# FT601.net
KiCad netlist of a schematic drawn in Altium Designer
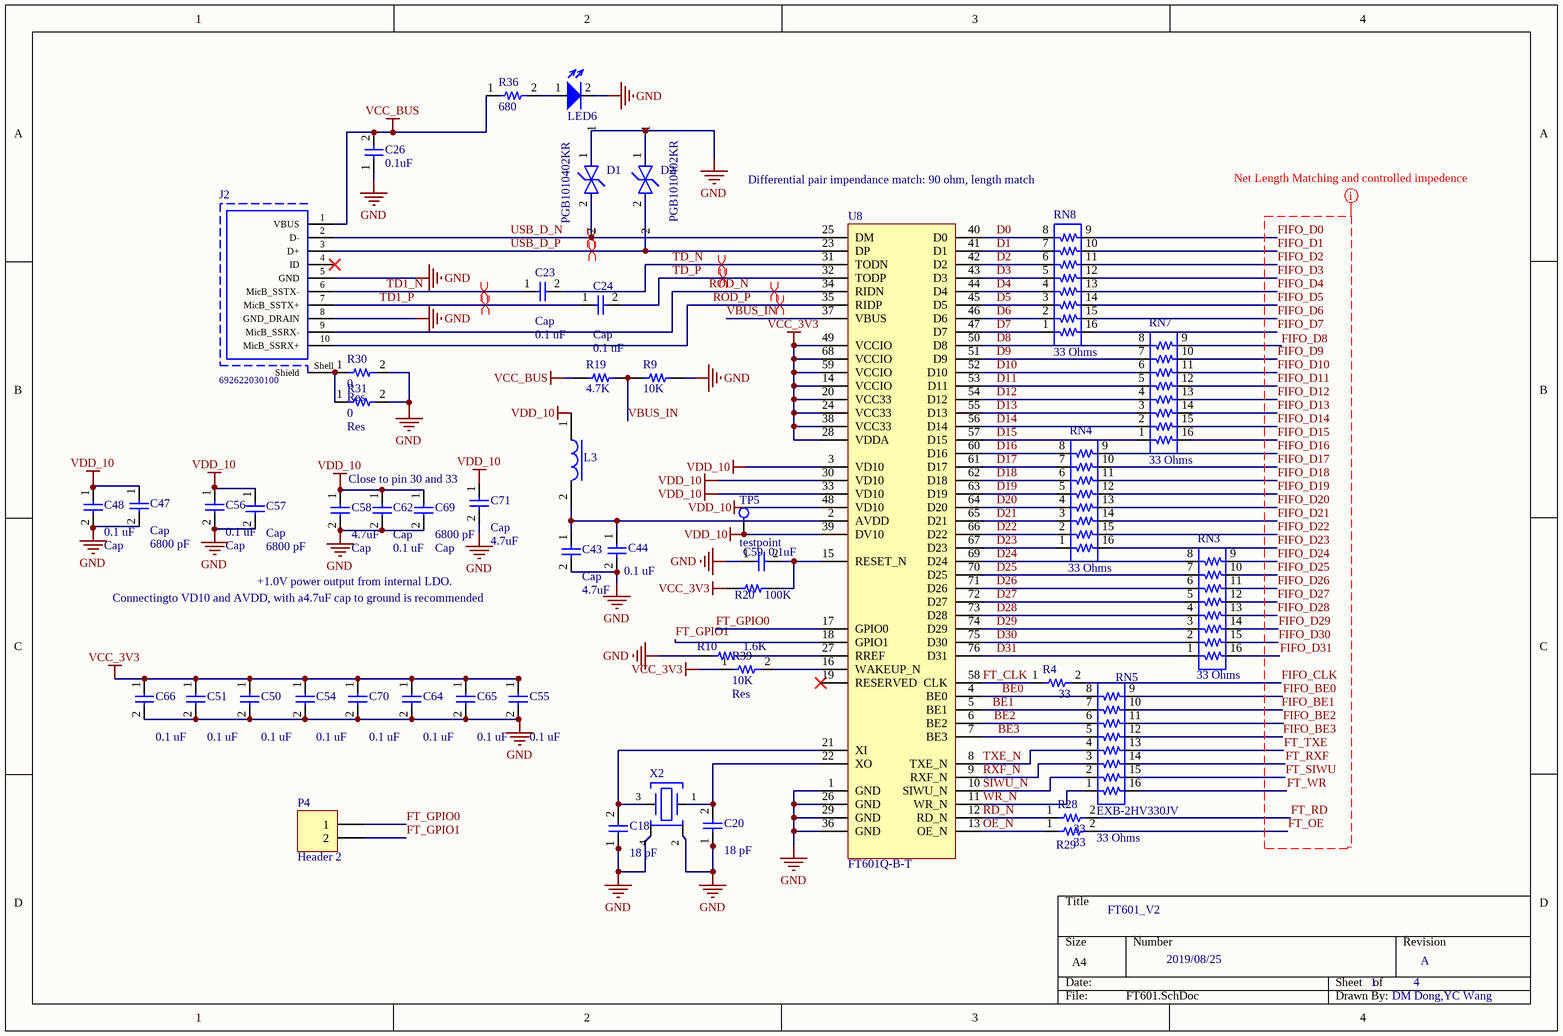
[diagram p0: FT601.SchDoc]

(export (version "E")
  (design (tool "Eeschema 10.0.6"))
  (components
    (comp (ref "C18")
      (value "18 pF")
      (footprint "CAP_18pF_0603")
      (description "Multilayer Ceramic Capacitors MLCC - SMD/SMT 50V 18pF 0603 X7R 10% AEC-Q200")
      (fields (field (name "Comment") "C0603C180K5RACAUTO"))
      (libsource (lib "USB_FPGA_SLM_v1") (part "Cap_18pF_0603"))
    )
    (comp (ref "C20")
      (value "18 pF")
      (footprint "CAP_18pF_0603")
      (description "Multilayer Ceramic Capacitors MLCC - SMD/SMT 50V 18pF 0603 X7R 10% AEC-Q200")
      (fields (field (name "Comment") "C0603C180K5RACAUTO"))
      (libsource (lib "USB_FPGA_SLM_v1") (part "Cap_18pF_0603"))
    )
    (comp (ref "C23")
      (value "0.1 uF")
      (footprint "Cap_0.1uF_0402")
      (description "Multilayer Ceramic Capacitors MLCC - SMD/SMT 100nF 10V X5R 10%")
      (fields
        (field (name "COMPONENT NAME") "Cap")
        (field (name "Comment") "CC0402KPX5R6BB104")
        (field (name "CREATED BY") "Daoming Dong")
      )
      (libsource (lib "USB_FPGA_SLM_v1") (part "CAP_0.1uF_0402"))
    )
    (comp (ref "C24")
      (value "0.1 uF")
      (footprint "Cap_0.1uF_0402")
      (description "Multilayer Ceramic Capacitors MLCC - SMD/SMT 100nF 10V X5R 10%")
      (fields
        (field (name "COMPONENT NAME") "Cap")
        (field (name "Comment") "CC0402KPX5R6BB104")
        (field (name "CREATED BY") "Daoming Dong")
      )
      (libsource (lib "USB_FPGA_SLM_v1") (part "CAP_0.1uF_0402"))
    )
    (comp (ref "C26")
      (value "0.1uF")
      (footprint "Cap_0.1uF")
      (description "Multilayer Ceramic Capacitors MLCC - SMD/SMT 0.1uF 10% 50V AEC-Q200")
      (fields (field (name "Comment") "AC0603KRX7R9BB104") (field (name "CREATED BY") "Daoming Dong"))
      (libsource (lib "USB_FPGA_SLM_v1") (part "Cap_0.1uF"))
    )
    (comp (ref "C43")
      (value "4.7uF")
      (footprint "CAP_4.7uF_0402")
      (description "Multilayer Ceramic Capacitors MLCC - SMD/SMT 0402 6.3V 4.7uF X5R 10% T: 0.5mm")
      (fields
        (field (name "COMPONENT NAME") "Cap")
        (field (name "Comment") "C1005X5R0J475K050BC")
        (field (name "CREATED BY") "Daoming Dong")
      )
      (libsource (lib "USB_FPGA_SLM_v1") (part "Cap_4.7uF_0402"))
    )
    (comp (ref "C44")
      (value "0.1 uF")
      (footprint "Cap_0.1uF_0402")
      (description "Multilayer Ceramic Capacitors MLCC - SMD/SMT 100nF 10V X5R 10%")
      (fields (field (name "Comment") "CC0402KPX5R6BB104") (field (name "CREATED BY") "Daoming Dong"))
      (libsource (lib "USB_FPGA_SLM_v1") (part "CAP_0.1uF_0402"))
    )
    (comp (ref "C47")
      (value "6800 pF")
      (footprint "CAP_6700pF_0402")
      (description "Multilayer Ceramic Capacitors MLCC - SMD/SMT 50V 6800pF X7R 0402 10% AEC-Q200")
      (fields
        (field (name "COMPONENT NAME") "Cap")
        (field (name "Comment") "C0402C682K5RECAUTO")
        (field (name "CREATED BY") "Daoming Dong")
      )
      (libsource (lib "USB_FPGA_SLM_v1") (part "Cap_6800pF_0402"))
    )
    (comp (ref "C48")
      (value "0.1 uF")
      (footprint "Cap_0.1uF_0402")
      (description "Multilayer Ceramic Capacitors MLCC - SMD/SMT 100nF 10V X5R 10%")
      (fields
        (field (name "COMPONENT NAME") "Cap")
        (field (name "Comment") "CC0402KPX5R6BB104")
        (field (name "CREATED BY") "Daoming Dong")
      )
      (libsource (lib "USB_FPGA_SLM_v1") (part "CAP_0.1uF_0402"))
    )
    (comp (ref "C50")
      (value "0.1 uF")
      (footprint "Cap_0.1uF_0402")
      (description "Multilayer Ceramic Capacitors MLCC - SMD/SMT 100nF 10V X5R 10%")
      (fields (field (name "Comment") "CC0402KPX5R6BB104") (field (name "CREATED BY") "Daoming Dong"))
      (libsource (lib "USB_FPGA_SLM_v1") (part "CAP_0.1uF_0402"))
    )
    (comp (ref "C51")
      (value "0.1 uF")
      (footprint "Cap_0.1uF_0402")
      (description "Multilayer Ceramic Capacitors MLCC - SMD/SMT 100nF 10V X5R 10%")
      (fields (field (name "Comment") "CC0402KPX5R6BB104") (field (name "CREATED BY") "Daoming Dong"))
      (libsource (lib "USB_FPGA_SLM_v1") (part "CAP_0.1uF_0402"))
    )
    (comp (ref "C54")
      (value "0.1 uF")
      (footprint "Cap_0.1uF_0402")
      (description "Multilayer Ceramic Capacitors MLCC - SMD/SMT 100nF 10V X5R 10%")
      (fields (field (name "Comment") "CC0402KPX5R6BB104") (field (name "CREATED BY") "Daoming Dong"))
      (libsource (lib "USB_FPGA_SLM_v1") (part "CAP_0.1uF_0402"))
    )
    (comp (ref "C55")
      (value "0.1 uF")
      (footprint "Cap_0.1uF_0402")
      (description "Multilayer Ceramic Capacitors MLCC - SMD/SMT 100nF 10V X5R 10%")
      (fields (field (name "Comment") "CC0402KPX5R6BB104") (field (name "CREATED BY") "Daoming Dong"))
      (libsource (lib "USB_FPGA_SLM_v1") (part "CAP_0.1uF_0402"))
    )
    (comp (ref "C56")
      (value "0.1 uF")
      (footprint "Cap_0.1uF_0402")
      (description "Multilayer Ceramic Capacitors MLCC - SMD/SMT 100nF 10V X5R 10%")
      (fields
        (field (name "COMPONENT NAME") "Cap")
        (field (name "Comment") "CC0402KPX5R6BB104")
        (field (name "CREATED BY") "Daoming Dong")
      )
      (libsource (lib "USB_FPGA_SLM_v1") (part "CAP_0.1uF_0402"))
    )
    (comp (ref "C57")
      (value "6800 pF")
      (footprint "CAP_6700pF_0402")
      (description "Multilayer Ceramic Capacitors MLCC - SMD/SMT 50V 6800pF X7R 0402 10% AEC-Q200")
      (fields
        (field (name "COMPONENT NAME") "Cap")
        (field (name "Comment") "C0402C682K5RECAUTO")
        (field (name "CREATED BY") "Daoming Dong")
      )
      (libsource (lib "USB_FPGA_SLM_v1") (part "Cap_6800pF_0402"))
    )
    (comp (ref "C58")
      (value "4.7uF")
      (footprint "CAP_4.7uF_0402")
      (description "Multilayer Ceramic Capacitors MLCC - SMD/SMT 0402 6.3V 4.7uF X5R 10% T: 0.5mm")
      (fields
        (field (name "COMPONENT NAME") "Cap")
        (field (name "Comment") "C1005X5R0J475K050BC")
        (field (name "CREATED BY") "Daoming Dong")
      )
      (libsource (lib "USB_FPGA_SLM_v1") (part "Cap_4.7uF_0402"))
    )
    (comp (ref "C59")
      (value "0.1uF")
      (footprint "Cap_0.1uF")
      (description "Multilayer Ceramic Capacitors MLCC - SMD/SMT 0.1uF 10% 50V AEC-Q200")
      (fields (field (name "Comment") "AC0603KRX7R9BB104") (field (name "CREATED BY") "Daoming Dong"))
      (libsource (lib "USB_FPGA_SLM_v1") (part "Cap_0.1uF"))
    )
    (comp (ref "C62")
      (value "0.1 uF")
      (footprint "Cap_0.1uF_0402")
      (description "Multilayer Ceramic Capacitors MLCC - SMD/SMT 100nF 10V X5R 10%")
      (fields
        (field (name "COMPONENT NAME") "Cap")
        (field (name "Comment") "CC0402KPX5R6BB104")
        (field (name "CREATED BY") "Daoming Dong")
      )
      (libsource (lib "USB_FPGA_SLM_v1") (part "CAP_0.1uF_0402"))
    )
    (comp (ref "C64")
      (value "0.1 uF")
      (footprint "Cap_0.1uF_0402")
      (description "Multilayer Ceramic Capacitors MLCC - SMD/SMT 100nF 10V X5R 10%")
      (fields (field (name "Comment") "CC0402KPX5R6BB104") (field (name "CREATED BY") "Daoming Dong"))
      (libsource (lib "USB_FPGA_SLM_v1") (part "CAP_0.1uF_0402"))
    )
    (comp (ref "C65")
      (value "0.1 uF")
      (footprint "Cap_0.1uF_0402")
      (description "Multilayer Ceramic Capacitors MLCC - SMD/SMT 100nF 10V X5R 10%")
      (fields (field (name "Comment") "CC0402KPX5R6BB104") (field (name "CREATED BY") "Daoming Dong"))
      (libsource (lib "USB_FPGA_SLM_v1") (part "CAP_0.1uF_0402"))
    )
    (comp (ref "C66")
      (value "0.1 uF")
      (footprint "Cap_0.1uF_0402")
      (description "Multilayer Ceramic Capacitors MLCC - SMD/SMT 100nF 10V X5R 10%")
      (fields (field (name "Comment") "CC0402KPX5R6BB104") (field (name "CREATED BY") "Daoming Dong"))
      (libsource (lib "USB_FPGA_SLM_v1") (part "CAP_0.1uF_0402"))
    )
    (comp (ref "C69")
      (value "6800 pF")
      (footprint "CAP_6700pF_0402")
      (description "Multilayer Ceramic Capacitors MLCC - SMD/SMT 50V 6800pF X7R 0402 10% AEC-Q200")
      (fields
        (field (name "COMPONENT NAME") "Cap")
        (field (name "Comment") "C0402C682K5RECAUTO")
        (field (name "CREATED BY") "Daoming Dong")
      )
      (libsource (lib "USB_FPGA_SLM_v1") (part "Cap_6800pF_0402"))
    )
    (comp (ref "C70")
      (value "0.1 uF")
      (footprint "Cap_0.1uF_0402")
      (description "Multilayer Ceramic Capacitors MLCC - SMD/SMT 100nF 10V X5R 10%")
      (fields (field (name "Comment") "CC0402KPX5R6BB104") (field (name "CREATED BY") "Daoming Dong"))
      (libsource (lib "USB_FPGA_SLM_v1") (part "CAP_0.1uF_0402"))
    )
    (comp (ref "C71")
      (value "4.7uF")
      (footprint "CAP_4.7uF_0402")
      (description "Multilayer Ceramic Capacitors MLCC - SMD/SMT 0402 6.3V 4.7uF X5R 10% T: 0.5mm")
      (fields
        (field (name "COMPONENT NAME") "Cap")
        (field (name "Comment") "C1005X5R0J475K050BC")
        (field (name "CREATED BY") "Daoming Dong")
      )
      (libsource (lib "USB_FPGA_SLM_v1") (part "Cap_4.7uF_0402"))
    )
    (comp (ref "D1")
      (value "PGB1010402KR")
      (footprint "ESD_Suppressor")
      (description "ESD Suppressors / TVS Diodes PULSEGUARD 0402 ESD SUPPRESSOR")
      (fields (field (name "CREATED BY") "Daoming Dong"))
      (libsource (lib "USB_FPGA_SLM_v1") (part "ESD_Suppresor"))
    )
    (comp (ref "D2")
      (value "PGB1010402KR")
      (footprint "ESD_Suppressor")
      (description "ESD Suppressors / TVS Diodes PULSEGUARD 0402 ESD SUPPRESSOR")
      (fields (field (name "CREATED BY") "Daoming Dong"))
      (libsource (lib "USB_FPGA_SLM_v1") (part "ESD_Suppresor"))
    )
    (comp (ref "J2")
      (value "692622030100")
      (footprint "692622030100")
      (description "Micro USB 3.0 Type B Receptacle WR-COM, Horizontal, SMT, with Pads")
      (fields (field (name "PUBLISHER") "Wurth Elektronik"))
      (libsource (lib "Altium_WR-COM_USB-Connectors (rev18d)") (part "692622030100"))
    )
    (comp (ref "L3")
      (value "BLM18PG300SZ1D")
      (footprint "FerriteBeads")
      (description "Ferrite Beads 0603 30ohms 1000mA Auto Infotainment")
      (fields (field (name "CREATED BY") "Daoming Dong"))
      (libsource (lib "USB_FPGA_SLM_v1") (part "FerriteBeadForFT601"))
    )
    (comp (ref "LED6")
      (value "TLMS1000-GS08")
      (footprint "LED_RED")
      (description "Standard LEDs - SMD RED")
      (fields (field (name "CREATED BY") "Daoming Dong"))
      (libsource (lib "USB_FPGA_SLM_v1") (part "LED_RED"))
    )
    (comp (ref "P4")
      (value "Header 2")
      (footprint "HDR1X2")
      (description "Header, 2-Pin")
      (fields (field (name "PUBLISHER") "Altium Limited"))
      (libsource (lib "Miscellaneous Connectors") (part "Header 2"))
    )
    (comp (ref "R4")
      (value "33")
      (footprint "Res_33_0402")
      (description "Thick Film Resistors - SMD 0402 Resistor 0.5% 100ppm 33Ohm")
      (fields (field (name "Comment") "ERJ2RKD33R0X") (field (name "CREATED BY.") "Daoming Dong"))
      (libsource (lib "USB_FPGA_SLM_v1") (part "Res_33_0402"))
    )
    (comp (ref "R9")
      (value "10K")
      (footprint "RES_10K")
      (description "Thin Film Resistors - SMD 10K ohm 0.05% 50 ppm High-Precision")
      (fields (field (name "Comment") "RT0603WRE0710KL") (field (name "CREATED BY") "Daoming Dong"))
      (libsource (lib "USB_FPGA_SLM_v1") (part "Res_10K"))
    )
    (comp (ref "R10")
      (value "1.6K")
      (footprint "RES_1.6K")
      (description "Thick Film Resistors - SMD 0603 Resistor 0.5% 50ppm 1.6KOhm")
      (fields (field (name "Comment") "ERJ-3RBD1601V") (field (name "CREATED BY") "Daoming Dong"))
      (libsource (lib "USB_FPGA_SLM_v1") (part "Res_1.6K"))
    )
    (comp (ref "R19")
      (value "4.7K")
      (footprint "RES_4.7K")
      (description "Thick Film Resistors - SMD 4.7K ohm 5% 1/10W AEC-Q200")
      (fields (field (name "Comment") "AC0603JR-134K7L") (field (name "CREATED BY") "Daoming Dong"))
      (libsource (lib "USB_FPGA_SLM_v1") (part "Res_4.7K"))
    )
    (comp (ref "R20")
      (value "100K")
      (footprint "RES_100K")
      (description "Thick Film Resistors - SMD 100K ohm 10% 75V AEC-Q200")
      (fields (field (name "Comment") "SR0603KR-07100KL") (field (name "CREATED BY") "Daoming Dong"))
      (libsource (lib "USB_FPGA_SLM_v1") (part "Res_100K"))
    )
    (comp (ref "R28")
      (value "33")
      (footprint "Res_33_0402")
      (description "Thick Film Resistors - SMD 0402 Resistor 0.5% 100ppm 33Ohm")
      (fields (field (name "Comment") "ERJ2RKD33R0X") (field (name "CREATED BY.") "Daoming Dong"))
      (libsource (lib "USB_FPGA_SLM_v1") (part "Res_33_0402"))
    )
    (comp (ref "R29")
      (value "33")
      (footprint "Res_33_0402")
      (description "Thick Film Resistors - SMD 0402 Resistor 0.5% 100ppm 33Ohm")
      (fields (field (name "Comment") "ERJ2RKD33R0X") (field (name "CREATED BY.") "Daoming Dong"))
      (libsource (lib "USB_FPGA_SLM_v1") (part "Res_33_0402"))
    )
    (comp (ref "R30")
      (value "0")
      (footprint "RES_0")
      (description "Thick Film Resistors - SMD 1/10Watt 0ohms Commercial Use")
      (fields
        (field (name "COMPONENT NAME") "Res")
        (field (name "Comment") "CRCW06030000Z0EAC")
        (field (name "CREATED BY") "Daoming Dong")
      )
      (libsource (lib "USB_FPGA_SLM_v1") (part "Res_0"))
    )
    (comp (ref "R31")
      (value "0")
      (footprint "RES_0")
      (description "Thick Film Resistors - SMD 1/10Watt 0ohms Commercial Use")
      (fields
        (field (name "COMPONENT NAME") "Res")
        (field (name "Comment") "CRCW06030000Z0EAC")
        (field (name "CREATED BY") "Daoming Dong")
      )
      (libsource (lib "USB_FPGA_SLM_v1") (part "Res_0"))
    )
    (comp (ref "R36")
      (value "680")
      (footprint "RES_680")
      (description "Thin Film Resistors - SMD 680 ohm 1% 50 ppm Thin Film")
      (fields (field (name "Comment") "RT0603FRE13680RL") (field (name "CREATED BY") "Daoming Dong"))
      (libsource (lib "USB_FPGA_SLM_v1") (part "Res_680"))
    )
    (comp (ref "R39")
      (value "10K")
      (footprint "RES_10K")
      (description "Thin Film Resistors - SMD 10K ohm 0.05% 50 ppm High-Precision")
      (fields
        (field (name "COMPONENT NAME") "Res")
        (field (name "Comment") "RT0603WRE0710KL")
        (field (name "CREATED BY") "Daoming Dong")
      )
      (libsource (lib "") (part "Res_10K_1"))
    )
    (comp (ref "RN3")
      (value "33 Ohms")
      (footprint "ResArray_0")
      (description "Resistor Networks & Arrays 33 OHM 5%")
      (fields (field (name "Comment") "EXB-2HV330JV"))
      (libsource (lib "USB_FPGA_SLM_v1") (part "ResArray"))
    )
    (comp (ref "RN4")
      (value "33 Ohms")
      (footprint "ResArray_0")
      (description "Resistor Networks & Arrays 33 OHM 5%")
      (fields (field (name "Comment") "EXB-2HV330JV"))
      (libsource (lib "USB_FPGA_SLM_v1") (part "ResArray"))
    )
    (comp (ref "RN5")
      (value "EXB-2HV330JV")
      (footprint "ResArray_0")
      (description "Resistor Networks & Arrays 33 OHM 5%")
      (fields (field (name "ALTIUM_VALUE") "33 Ohms"))
      (libsource (lib "USB_FPGA_SLM_v1") (part "ResArray"))
    )
    (comp (ref "RN7")
      (value "33 Ohms")
      (footprint "ResArray_0")
      (description "Resistor Networks & Arrays 33 OHM 5%")
      (fields (field (name "Comment") "EXB-2HV330JV"))
      (libsource (lib "USB_FPGA_SLM_v1") (part "ResArray"))
    )
    (comp (ref "RN8")
      (value "33 Ohms")
      (footprint "ResArray_0")
      (description "Resistor Networks & Arrays 33 OHM 5%")
      (fields (field (name "Comment") "EXB-2HV330JV"))
      (libsource (lib "USB_FPGA_SLM_v1") (part "ResArray"))
    )
    (comp (ref "TP5")
      (value "testpoint")
      (footprint "testpoint")
      (description "Testpoint for testing voltage")
      (fields (field (name "CREATED BY") "Daoming Dong"))
      (libsource (lib "USB_FPGA_SLM_v1") (part "Testpoint"))
    )
    (comp (ref "U8")
      (value "FT601Q-B-T")
      (footprint "FT601_NoGND_Pad")
      (description "USB Interface IC USB 3.0 Super-Speed 32Bits Sync FIFO")
      (fields (field (name "CREATED BY") "Daoming Dong"))
      (libsource (lib "USB_FPGA_SLM_v1") (part "FT601Q-B-T"))
    )
    (comp (ref "X2")
      (value "ABM8G-30.000MHZ-18-D2Y-T")
      (footprint "30MHzOscillatorV2")
      (description "Crystals 30.000MHz 18pF 30ppm -40C +85C")
      (fields (field (name "CREATED BY") "Youchao Wang"))
      (libsource (lib "USB_FPGA_SLM_v1") (part "30MHzOscillator"))
    )
  )
  (nets
    (net (code "1") (name "/BE0") (class "Default")
      (node (ref "RN5") (pin "8") (pinfunction "8_8") (pintype "passive"))
      (node (ref "U8") (pin "4") (pinfunction "BE0_4") (pintype "passive"))
    )
    (net (code "2") (name "/BE1") (class "Default")
      (node (ref "RN5") (pin "7") (pinfunction "7_7") (pintype "passive"))
      (node (ref "U8") (pin "5") (pinfunction "BE1_5") (pintype "passive"))
    )
    (net (code "3") (name "/BE2") (class "Default")
      (node (ref "RN5") (pin "6") (pinfunction "6_6") (pintype "passive"))
      (node (ref "U8") (pin "6") (pinfunction "BE2_6") (pintype "passive"))
    )
    (net (code "4") (name "/BE3") (class "Default")
      (node (ref "RN5") (pin "5") (pinfunction "5_5") (pintype "passive"))
      (node (ref "U8") (pin "7") (pinfunction "BE3_7") (pintype "passive"))
    )
    (net (code "5") (name "/D0") (class "Default")
      (node (ref "RN8") (pin "8") (pinfunction "8_8") (pintype "passive"))
      (node (ref "U8") (pin "40") (pinfunction "D0_40") (pintype "passive"))
    )
    (net (code "6") (name "/D1") (class "Default")
      (node (ref "RN8") (pin "7") (pinfunction "7_7") (pintype "passive"))
      (node (ref "U8") (pin "41") (pinfunction "D1_41") (pintype "passive"))
    )
    (net (code "7") (name "/D2") (class "Default")
      (node (ref "RN8") (pin "6") (pinfunction "6_6") (pintype "passive"))
      (node (ref "U8") (pin "42") (pinfunction "D2_42") (pintype "passive"))
    )
    (net (code "8") (name "/D3") (class "Default")
      (node (ref "RN8") (pin "5") (pinfunction "5_5") (pintype "passive"))
      (node (ref "U8") (pin "43") (pinfunction "D3_43") (pintype "passive"))
    )
    (net (code "9") (name "/D4") (class "Default")
      (node (ref "RN8") (pin "4") (pinfunction "4_4") (pintype "passive"))
      (node (ref "U8") (pin "44") (pinfunction "D4_44") (pintype "passive"))
    )
    (net (code "10") (name "/D5") (class "Default")
      (node (ref "RN8") (pin "3") (pinfunction "3_3") (pintype "passive"))
      (node (ref "U8") (pin "45") (pinfunction "D5_45") (pintype "passive"))
    )
    (net (code "11") (name "/D6") (class "Default")
      (node (ref "RN8") (pin "2") (pinfunction "2_2") (pintype "passive"))
      (node (ref "U8") (pin "46") (pinfunction "D6_46") (pintype "passive"))
    )
    (net (code "12") (name "/D7") (class "Default")
      (node (ref "RN8") (pin "1") (pinfunction "1_1") (pintype "passive"))
      (node (ref "U8") (pin "47") (pinfunction "D7_47") (pintype "passive"))
    )
    (net (code "13") (name "/D8") (class "Default")
      (node (ref "RN7") (pin "8") (pinfunction "8_8") (pintype "passive"))
      (node (ref "U8") (pin "50") (pinfunction "D8_50") (pintype "passive"))
    )
    (net (code "14") (name "/D9") (class "Default")
      (node (ref "RN7") (pin "7") (pinfunction "7_7") (pintype "passive"))
      (node (ref "U8") (pin "51") (pinfunction "D9_51") (pintype "passive"))
    )
    (net (code "15") (name "/D10") (class "Default")
      (node (ref "RN7") (pin "6") (pinfunction "6_6") (pintype "passive"))
      (node (ref "U8") (pin "52") (pinfunction "D10_52") (pintype "passive"))
    )
    (net (code "16") (name "/D11") (class "Default")
      (node (ref "RN7") (pin "5") (pinfunction "5_5") (pintype "passive"))
      (node (ref "U8") (pin "53") (pinfunction "D11_53") (pintype "passive"))
    )
    (net (code "17") (name "/D12") (class "Default")
      (node (ref "RN7") (pin "4") (pinfunction "4_4") (pintype "passive"))
      (node (ref "U8") (pin "54") (pinfunction "D12_54") (pintype "passive"))
    )
    (net (code "18") (name "/D13") (class "Default")
      (node (ref "RN7") (pin "3") (pinfunction "3_3") (pintype "passive"))
      (node (ref "U8") (pin "55") (pinfunction "D13_55") (pintype "passive"))
    )
    (net (code "19") (name "/D14") (class "Default")
      (node (ref "RN7") (pin "2") (pinfunction "2_2") (pintype "passive"))
      (node (ref "U8") (pin "56") (pinfunction "D14_56") (pintype "passive"))
    )
    (net (code "20") (name "/D15") (class "Default")
      (node (ref "RN7") (pin "1") (pinfunction "1_1") (pintype "passive"))
      (node (ref "U8") (pin "57") (pinfunction "D15_57") (pintype "passive"))
    )
    (net (code "21") (name "/D16") (class "Default")
      (node (ref "RN4") (pin "8") (pinfunction "8_8") (pintype "passive"))
      (node (ref "U8") (pin "60") (pinfunction "D16_60") (pintype "passive"))
    )
    (net (code "22") (name "/D17") (class "Default")
      (node (ref "RN4") (pin "7") (pinfunction "7_7") (pintype "passive"))
      (node (ref "U8") (pin "61") (pinfunction "D17_61") (pintype "passive"))
    )
    (net (code "23") (name "/D18") (class "Default")
      (node (ref "RN4") (pin "6") (pinfunction "6_6") (pintype "passive"))
      (node (ref "U8") (pin "62") (pinfunction "D18_62") (pintype "passive"))
    )
    (net (code "24") (name "/D19") (class "Default")
      (node (ref "RN4") (pin "5") (pinfunction "5_5") (pintype "passive"))
      (node (ref "U8") (pin "63") (pinfunction "D19_63") (pintype "passive"))
    )
    (net (code "25") (name "/D20") (class "Default")
      (node (ref "RN4") (pin "4") (pinfunction "4_4") (pintype "passive"))
      (node (ref "U8") (pin "64") (pinfunction "D20_64") (pintype "passive"))
    )
    (net (code "26") (name "/D21") (class "Default")
      (node (ref "RN4") (pin "3") (pinfunction "3_3") (pintype "passive"))
      (node (ref "U8") (pin "65") (pinfunction "D21_65") (pintype "passive"))
    )
    (net (code "27") (name "/D22") (class "Default")
      (node (ref "RN4") (pin "2") (pinfunction "2_2") (pintype "passive"))
      (node (ref "U8") (pin "66") (pinfunction "D22_66") (pintype "passive"))
    )
    (net (code "28") (name "/D23") (class "Default")
      (node (ref "RN4") (pin "1") (pinfunction "1_1") (pintype "passive"))
      (node (ref "U8") (pin "67") (pinfunction "D23_67") (pintype "passive"))
    )
    (net (code "29") (name "/D24") (class "Default")
      (node (ref "RN3") (pin "8") (pinfunction "8_8") (pintype "passive"))
      (node (ref "U8") (pin "69") (pinfunction "D24_69") (pintype "passive"))
    )
    (net (code "30") (name "/D25") (class "Default")
      (node (ref "RN3") (pin "7") (pinfunction "7_7") (pintype "passive"))
      (node (ref "U8") (pin "70") (pinfunction "D25_70") (pintype "passive"))
    )
    (net (code "31") (name "/D26") (class "Default")
      (node (ref "RN3") (pin "6") (pinfunction "6_6") (pintype "passive"))
      (node (ref "U8") (pin "71") (pinfunction "D26_71") (pintype "passive"))
    )
    (net (code "32") (name "/D27") (class "Default")
      (node (ref "RN3") (pin "5") (pinfunction "5_5") (pintype "passive"))
      (node (ref "U8") (pin "72") (pinfunction "D27_72") (pintype "passive"))
    )
    (net (code "33") (name "/D28") (class "Default")
      (node (ref "RN3") (pin "4") (pinfunction "4_4") (pintype "passive"))
      (node (ref "U8") (pin "73") (pinfunction "D28_73") (pintype "passive"))
    )
    (net (code "34") (name "/D29") (class "Default")
      (node (ref "RN3") (pin "3") (pinfunction "3_3") (pintype "passive"))
      (node (ref "U8") (pin "74") (pinfunction "D29_74") (pintype "passive"))
    )
    (net (code "35") (name "/D30") (class "Default")
      (node (ref "RN3") (pin "2") (pinfunction "2_2") (pintype "passive"))
      (node (ref "U8") (pin "75") (pinfunction "D30_75") (pintype "passive"))
    )
    (net (code "36") (name "/D31") (class "Default")
      (node (ref "RN3") (pin "1") (pinfunction "1_1") (pintype "passive"))
      (node (ref "U8") (pin "76") (pinfunction "D31_76") (pintype "passive"))
    )
    (net (code "37") (name "/FIFO_BE0") (class "Default")
      (node (ref "RN5") (pin "9") (pinfunction "9_9") (pintype "passive"))
    )
    (net (code "38") (name "/FIFO_BE1") (class "Default")
      (node (ref "RN5") (pin "10") (pinfunction "10_10") (pintype "passive"))
    )
    (net (code "39") (name "/FIFO_BE2") (class "Default")
      (node (ref "RN5") (pin "11") (pinfunction "11_11") (pintype "passive"))
    )
    (net (code "40") (name "/FIFO_BE3") (class "Default")
      (node (ref "RN5") (pin "12") (pinfunction "12_12") (pintype "passive"))
    )
    (net (code "41") (name "/FIFO_CLK") (class "Default")
      (node (ref "R4") (pin "2") (pinfunction "2_2") (pintype "passive"))
    )
    (net (code "42") (name "/FIFO_D0") (class "Default")
      (node (ref "RN8") (pin "9") (pinfunction "9_9") (pintype "passive"))
    )
    (net (code "43") (name "/FIFO_D1") (class "Default")
      (node (ref "RN8") (pin "10") (pinfunction "10_10") (pintype "passive"))
    )
    (net (code "44") (name "/FIFO_D2") (class "Default")
      (node (ref "RN8") (pin "11") (pinfunction "11_11") (pintype "passive"))
    )
    (net (code "45") (name "/FIFO_D3") (class "Default")
      (node (ref "RN8") (pin "12") (pinfunction "12_12") (pintype "passive"))
    )
    (net (code "46") (name "/FIFO_D4") (class "Default")
      (node (ref "RN8") (pin "13") (pinfunction "13_13") (pintype "passive"))
    )
    (net (code "47") (name "/FIFO_D5") (class "Default")
      (node (ref "RN8") (pin "14") (pinfunction "14_14") (pintype "passive"))
    )
    (net (code "48") (name "/FIFO_D6") (class "Default")
      (node (ref "RN8") (pin "15") (pinfunction "15_15") (pintype "passive"))
    )
    (net (code "49") (name "/FIFO_D7") (class "Default")
      (node (ref "RN8") (pin "16") (pinfunction "16_16") (pintype "passive"))
    )
    (net (code "50") (name "/FIFO_D8") (class "Default")
      (node (ref "RN7") (pin "9") (pinfunction "9_9") (pintype "passive"))
    )
    (net (code "51") (name "/FIFO_D9") (class "Default")
      (node (ref "RN7") (pin "10") (pinfunction "10_10") (pintype "passive"))
    )
    (net (code "52") (name "/FIFO_D10") (class "Default")
      (node (ref "RN7") (pin "11") (pinfunction "11_11") (pintype "passive"))
    )
    (net (code "53") (name "/FIFO_D11") (class "Default")
      (node (ref "RN7") (pin "12") (pinfunction "12_12") (pintype "passive"))
    )
    (net (code "54") (name "/FIFO_D12") (class "Default")
      (node (ref "RN7") (pin "13") (pinfunction "13_13") (pintype "passive"))
    )
    (net (code "55") (name "/FIFO_D13") (class "Default")
      (node (ref "RN7") (pin "14") (pinfunction "14_14") (pintype "passive"))
    )
    (net (code "56") (name "/FIFO_D14") (class "Default")
      (node (ref "RN7") (pin "15") (pinfunction "15_15") (pintype "passive"))
    )
    (net (code "57") (name "/FIFO_D15") (class "Default")
      (node (ref "RN7") (pin "16") (pinfunction "16_16") (pintype "passive"))
    )
    (net (code "58") (name "/FIFO_D16") (class "Default")
      (node (ref "RN4") (pin "9") (pinfunction "9_9") (pintype "passive"))
    )
    (net (code "59") (name "/FIFO_D17") (class "Default")
      (node (ref "RN4") (pin "10") (pinfunction "10_10") (pintype "passive"))
    )
    (net (code "60") (name "/FIFO_D18") (class "Default")
      (node (ref "RN4") (pin "11") (pinfunction "11_11") (pintype "passive"))
    )
    (net (code "61") (name "/FIFO_D19") (class "Default")
      (node (ref "RN4") (pin "12") (pinfunction "12_12") (pintype "passive"))
    )
    (net (code "62") (name "/FIFO_D20") (class "Default")
      (node (ref "RN4") (pin "13") (pinfunction "13_13") (pintype "passive"))
    )
    (net (code "63") (name "/FIFO_D21") (class "Default")
      (node (ref "RN4") (pin "14") (pinfunction "14_14") (pintype "passive"))
    )
    (net (code "64") (name "/FIFO_D22") (class "Default")
      (node (ref "RN4") (pin "15") (pinfunction "15_15") (pintype "passive"))
    )
    (net (code "65") (name "/FIFO_D23") (class "Default")
      (node (ref "RN4") (pin "16") (pinfunction "16_16") (pintype "passive"))
    )
    (net (code "66") (name "/FIFO_D24") (class "Default")
      (node (ref "RN3") (pin "9") (pinfunction "9_9") (pintype "passive"))
    )
    (net (code "67") (name "/FIFO_D25") (class "Default")
      (node (ref "RN3") (pin "10") (pinfunction "10_10") (pintype "passive"))
    )
    (net (code "68") (name "/FIFO_D26") (class "Default")
      (node (ref "RN3") (pin "11") (pinfunction "11_11") (pintype "passive"))
    )
    (net (code "69") (name "/FIFO_D27") (class "Default")
      (node (ref "RN3") (pin "12") (pinfunction "12_12") (pintype "passive"))
    )
    (net (code "70") (name "/FIFO_D28") (class "Default")
      (node (ref "RN3") (pin "13") (pinfunction "13_13") (pintype "passive"))
    )
    (net (code "71") (name "/FIFO_D29") (class "Default")
      (node (ref "RN3") (pin "14") (pinfunction "14_14") (pintype "passive"))
    )
    (net (code "72") (name "/FIFO_D30") (class "Default")
      (node (ref "RN3") (pin "15") (pinfunction "15_15") (pintype "passive"))
    )
    (net (code "73") (name "/FIFO_D31") (class "Default")
      (node (ref "RN3") (pin "16") (pinfunction "16_16") (pintype "passive"))
    )
    (net (code "74") (name "/FT_CLK") (class "Default")
      (node (ref "R4") (pin "1") (pinfunction "1_1") (pintype "passive"))
      (node (ref "U8") (pin "58") (pinfunction "CLK_58") (pintype "passive"))
    )
    (net (code "75") (name "/FT_GPIO0") (class "Default")
      (node (ref "P4") (pin "1") (pinfunction "1_1") (pintype "passive"))
      (node (ref "U8") (pin "17") (pinfunction "GPIO0_17") (pintype "passive"))
    )
    (net (code "76") (name "/FT_GPIO1") (class "Default")
      (node (ref "P4") (pin "2") (pinfunction "2_2") (pintype "passive"))
      (node (ref "U8") (pin "18") (pinfunction "GPIO1_18") (pintype "passive"))
    )
    (net (code "77") (name "/FT_OE") (class "Default")
      (node (ref "R29") (pin "2") (pinfunction "2_2") (pintype "passive"))
    )
    (net (code "78") (name "/FT_RD") (class "Default")
      (node (ref "R28") (pin "2") (pinfunction "2_2") (pintype "passive"))
    )
    (net (code "79") (name "/FT_RXF") (class "Default")
      (node (ref "RN5") (pin "14") (pinfunction "14_14") (pintype "passive"))
    )
    (net (code "80") (name "/FT_SIWU") (class "Default")
      (node (ref "RN5") (pin "15") (pinfunction "15_15") (pintype "passive"))
    )
    (net (code "81") (name "/FT_TXE") (class "Default")
      (node (ref "RN5") (pin "13") (pinfunction "13_13") (pintype "passive"))
    )
    (net (code "82") (name "/FT_WR") (class "Default")
      (node (ref "RN5") (pin "16") (pinfunction "16_16") (pintype "passive"))
    )
    (net (code "83") (name "/OE_N") (class "Default")
      (node (ref "R29") (pin "1") (pinfunction "1_1") (pintype "passive"))
      (node (ref "U8") (pin "13") (pinfunction "OE_N_13") (pintype "passive"))
    )
    (net (code "84") (name "/RD_N") (class "Default")
      (node (ref "R28") (pin "1") (pinfunction "1_1") (pintype "passive"))
      (node (ref "U8") (pin "12") (pinfunction "RD_N_12") (pintype "passive"))
    )
    (net (code "85") (name "/ROD_N") (class "Default")
      (node (ref "J2") (pin "9") (pinfunction "MicB_SSRX-_9") (pintype "passive"))
      (node (ref "U8") (pin "34") (pinfunction "RIDN_34") (pintype "passive"))
    )
    (net (code "86") (name "/ROD_P") (class "Default")
      (node (ref "J2") (pin "10") (pinfunction "MicB_SSRX+_10") (pintype "passive"))
      (node (ref "U8") (pin "35") (pinfunction "RIDP_35") (pintype "passive"))
    )
    (net (code "87") (name "/RXF_N") (class "Default")
      (node (ref "RN5") (pin "3") (pinfunction "3_3") (pintype "passive"))
      (node (ref "U8") (pin "9") (pinfunction "RXF_N_9") (pintype "passive"))
    )
    (net (code "88") (name "/SIWU_N") (class "Default")
      (node (ref "RN5") (pin "2") (pinfunction "2_2") (pintype "passive"))
      (node (ref "U8") (pin "10") (pinfunction "SIWU_N_10") (pintype "passive"))
    )
    (net (code "89") (name "/TD1_N") (class "Default")
      (node (ref "C23") (pin "1") (pinfunction "1_1") (pintype "passive"))
      (node (ref "J2") (pin "6") (pinfunction "MicB_SSTX-_6") (pintype "passive"))
    )
    (net (code "90") (name "/TD1_P") (class "Default")
      (node (ref "C24") (pin "1") (pinfunction "1_1") (pintype "passive"))
      (node (ref "J2") (pin "7") (pinfunction "MicB_SSTX+_7") (pintype "passive"))
    )
    (net (code "91") (name "/TD_N") (class "Default")
      (node (ref "C23") (pin "2") (pinfunction "2_2") (pintype "passive"))
      (node (ref "U8") (pin "31") (pinfunction "TODN_31") (pintype "passive"))
    )
    (net (code "92") (name "/TD_P") (class "Default")
      (node (ref "C24") (pin "2") (pinfunction "2_2") (pintype "passive"))
      (node (ref "U8") (pin "32") (pinfunction "TODP_32") (pintype "passive"))
    )
    (net (code "93") (name "/TXE_N") (class "Default")
      (node (ref "RN5") (pin "4") (pinfunction "4_4") (pintype "passive"))
      (node (ref "U8") (pin "8") (pinfunction "TXE_N_8") (pintype "passive"))
    )
    (net (code "94") (name "/USB_D_N") (class "Default")
      (node (ref "D1") (pin "2") (pinfunction "2_2") (pintype "passive"))
      (node (ref "J2") (pin "2") (pinfunction "D-_2") (pintype "passive"))
      (node (ref "U8") (pin "25") (pinfunction "DM_25") (pintype "passive"))
    )
    (net (code "95") (name "/USB_D_P") (class "Default")
      (node (ref "D2") (pin "2") (pinfunction "2_2") (pintype "passive"))
      (node (ref "J2") (pin "3") (pinfunction "D+_3") (pintype "passive"))
      (node (ref "U8") (pin "23") (pinfunction "DP_23") (pintype "passive"))
    )
    (net (code "96") (name "/VBUS_IN") (class "Default")
      (node (ref "R19") (pin "1") (pinfunction "1_1") (pintype "passive"))
      (node (ref "R9") (pin "2") (pinfunction "2_2") (pintype "passive"))
      (node (ref "U8") (pin "37") (pinfunction "VBUS_37") (pintype "passive"))
    )
    (net (code "97") (name "/WR_N") (class "Default")
      (node (ref "RN5") (pin "1") (pinfunction "1_1") (pintype "passive"))
      (node (ref "U8") (pin "11") (pinfunction "WR_N_11") (pintype "passive"))
    )
    (net (code "98") (name "GND") (class "Default")
      (node (ref "C18") (pin "1") (pinfunction "1_1") (pintype "passive"))
      (node (ref "C20") (pin "1") (pinfunction "1_1") (pintype "passive"))
      (node (ref "C26") (pin "1") (pinfunction "1_1") (pintype "passive"))
      (node (ref "C43") (pin "2") (pinfunction "2_2") (pintype "passive"))
      (node (ref "C44") (pin "2") (pinfunction "2_2") (pintype "passive"))
      (node (ref "C47") (pin "2") (pinfunction "2_2") (pintype "passive"))
      (node (ref "C48") (pin "2") (pinfunction "2_2") (pintype "passive"))
      (node (ref "C50") (pin "2") (pinfunction "2_2") (pintype "passive"))
      (node (ref "C51") (pin "2") (pinfunction "2_2") (pintype "passive"))
      (node (ref "C54") (pin "2") (pinfunction "2_2") (pintype "passive"))
      (node (ref "C55") (pin "2") (pinfunction "2_2") (pintype "passive"))
      (node (ref "C56") (pin "2") (pinfunction "2_2") (pintype "passive"))
      (node (ref "C57") (pin "2") (pinfunction "2_2") (pintype "passive"))
      (node (ref "C58") (pin "2") (pinfunction "2_2") (pintype "passive"))
      (node (ref "C59") (pin "1") (pinfunction "1_1") (pintype "passive"))
      (node (ref "C62") (pin "2") (pinfunction "2_2") (pintype "passive"))
      (node (ref "C64") (pin "2") (pinfunction "2_2") (pintype "passive"))
      (node (ref "C65") (pin "2") (pinfunction "2_2") (pintype "passive"))
      (node (ref "C66") (pin "2") (pinfunction "2_2") (pintype "passive"))
      (node (ref "C69") (pin "2") (pinfunction "2_2") (pintype "passive"))
      (node (ref "C70") (pin "2") (pinfunction "2_2") (pintype "passive"))
      (node (ref "C71") (pin "2") (pinfunction "2_2") (pintype "passive"))
      (node (ref "D1") (pin "1") (pinfunction "1_1") (pintype "passive"))
      (node (ref "D2") (pin "1") (pinfunction "1_1") (pintype "passive"))
      (node (ref "J2") (pin "5") (pinfunction "GND_5") (pintype "passive"))
      (node (ref "J2") (pin "8") (pinfunction "GND_DRAIN_8") (pintype "passive"))
      (node (ref "LED6") (pin "2") (pinfunction "Cathode_2") (pintype "passive"))
      (node (ref "R10") (pin "1") (pinfunction "1_1") (pintype "passive"))
      (node (ref "R30") (pin "2") (pinfunction "2_2") (pintype "passive"))
      (node (ref "R31") (pin "2") (pinfunction "2_2") (pintype "passive"))
      (node (ref "R9") (pin "1") (pinfunction "1_1") (pintype "passive"))
      (node (ref "U8") (pin "1") (pinfunction "GND_1") (pintype "passive"))
      (node (ref "U8") (pin "26") (pinfunction "GND_26") (pintype "passive"))
      (node (ref "U8") (pin "29") (pinfunction "GND_29") (pintype "passive"))
      (node (ref "U8") (pin "36") (pinfunction "GND_36") (pintype "passive"))
      (node (ref "X2") (pin "2") (pinfunction "GND_2") (pintype "passive"))
      (node (ref "X2") (pin "4") (pinfunction "GND_4") (pintype "passive"))
    )
    (net (code "99") (name "Net-(J2-Shield)") (class "Default")
      (node (ref "J2") (pin "Shell") (pinfunction "Shield_Shell") (pintype "passive"))
      (node (ref "R30") (pin "1") (pinfunction "1_1") (pintype "passive"))
      (node (ref "R31") (pin "1") (pinfunction "1_1") (pintype "passive"))
    )
    (net (code "100") (name "Net-(LED6-Anode)") (class "Default")
      (node (ref "LED6") (pin "1") (pinfunction "Anode_1") (pintype "passive"))
      (node (ref "R36") (pin "2") (pinfunction "2_2") (pintype "passive"))
    )
    (net (code "101") (name "Net-(U8-AVDD)") (class "Default")
      (node (ref "C43") (pin "1") (pinfunction "1_1") (pintype "passive"))
      (node (ref "C44") (pin "1") (pinfunction "1_1") (pintype "passive"))
      (node (ref "L3") (pin "2") (pinfunction "2_2") (pintype "passive"))
      (node (ref "U8") (pin "2") (pinfunction "AVDD_2") (pintype "passive"))
    )
    (net (code "102") (name "Net-(U8-RESET_N)") (class "Default")
      (node (ref "C59") (pin "2") (pinfunction "2_2") (pintype "passive"))
      (node (ref "R20") (pin "2") (pinfunction "2_2") (pintype "passive"))
      (node (ref "U8") (pin "15") (pinfunction "RESET_N_15") (pintype "passive"))
    )
    (net (code "103") (name "Net-(U8-RREF)") (class "Default")
      (node (ref "R10") (pin "2") (pinfunction "2_2") (pintype "passive"))
      (node (ref "U8") (pin "27") (pinfunction "RREF_27") (pintype "passive"))
    )
    (net (code "104") (name "Net-(U8-WAKEUP_N)") (class "Default")
      (node (ref "R39") (pin "2") (pinfunction "2_2") (pintype "passive"))
      (node (ref "U8") (pin "16") (pinfunction "WAKEUP_N_16") (pintype "passive"))
    )
    (net (code "105") (name "Net-(U8-XI)") (class "Default")
      (node (ref "C18") (pin "2") (pinfunction "2_2") (pintype "passive"))
      (node (ref "U8") (pin "21") (pinfunction "XI_21") (pintype "passive"))
      (node (ref "X2") (pin "3") (pinfunction "HOT_3") (pintype "passive"))
    )
    (net (code "106") (name "Net-(U8-XO)") (class "Default")
      (node (ref "C20") (pin "2") (pinfunction "2_2") (pintype "passive"))
      (node (ref "U8") (pin "22") (pinfunction "XO_22") (pintype "passive"))
      (node (ref "X2") (pin "1") (pinfunction "HOT_1") (pintype "passive"))
    )
    (net (code "107") (name "VCC_3V3") (class "Default")
      (node (ref "C50") (pin "1") (pinfunction "1_1") (pintype "passive"))
      (node (ref "C51") (pin "1") (pinfunction "1_1") (pintype "passive"))
      (node (ref "C54") (pin "1") (pinfunction "1_1") (pintype "passive"))
      (node (ref "C55") (pin "1") (pinfunction "1_1") (pintype "passive"))
      (node (ref "C64") (pin "1") (pinfunction "1_1") (pintype "passive"))
      (node (ref "C65") (pin "1") (pinfunction "1_1") (pintype "passive"))
      (node (ref "C66") (pin "1") (pinfunction "1_1") (pintype "passive"))
      (node (ref "C70") (pin "1") (pinfunction "1_1") (pintype "passive"))
      (node (ref "R20") (pin "1") (pinfunction "1_1") (pintype "passive"))
      (node (ref "R39") (pin "1") (pinfunction "1_1") (pintype "passive"))
      (node (ref "U8") (pin "14") (pinfunction "VCCIO_14") (pintype "passive"))
      (node (ref "U8") (pin "20") (pinfunction "VCC33_20") (pintype "passive"))
      (node (ref "U8") (pin "24") (pinfunction "VCC33_24") (pintype "passive"))
      (node (ref "U8") (pin "28") (pinfunction "VDDA_28") (pintype "passive"))
      (node (ref "U8") (pin "38") (pinfunction "VCC33_38") (pintype "passive"))
      (node (ref "U8") (pin "49") (pinfunction "VCCIO_49") (pintype "passive"))
      (node (ref "U8") (pin "59") (pinfunction "VCCIO_59") (pintype "passive"))
      (node (ref "U8") (pin "68") (pinfunction "VCCIO_68") (pintype "passive"))
    )
    (net (code "108") (name "VCC_BUS") (class "Default")
      (node (ref "C26") (pin "2") (pinfunction "2_2") (pintype "passive"))
      (node (ref "J2") (pin "1") (pinfunction "VBUS_1") (pintype "passive"))
      (node (ref "R19") (pin "2") (pinfunction "2_2") (pintype "passive"))
      (node (ref "R36") (pin "1") (pinfunction "1_1") (pintype "passive"))
    )
    (net (code "109") (name "VDD_10") (class "Default")
      (node (ref "C47") (pin "1") (pinfunction "1_1") (pintype "passive"))
      (node (ref "C48") (pin "1") (pinfunction "1_1") (pintype "passive"))
      (node (ref "C56") (pin "1") (pinfunction "1_1") (pintype "passive"))
      (node (ref "C57") (pin "1") (pinfunction "1_1") (pintype "passive"))
      (node (ref "C58") (pin "1") (pinfunction "1_1") (pintype "passive"))
      (node (ref "C62") (pin "1") (pinfunction "1_1") (pintype "passive"))
      (node (ref "C69") (pin "1") (pinfunction "1_1") (pintype "passive"))
      (node (ref "C71") (pin "1") (pinfunction "1_1") (pintype "passive"))
      (node (ref "L3") (pin "1") (pinfunction "1_1") (pintype "passive"))
      (node (ref "TP5") (pin "1") (pinfunction "1_1") (pintype "passive"))
      (node (ref "U8") (pin "3") (pinfunction "VD10_3") (pintype "passive"))
      (node (ref "U8") (pin "30") (pinfunction "VD10_30") (pintype "passive"))
      (node (ref "U8") (pin "33") (pinfunction "VD10_33") (pintype "passive"))
      (node (ref "U8") (pin "39") (pinfunction "DV10_39") (pintype "passive"))
      (node (ref "U8") (pin "48") (pinfunction "VD10_48") (pintype "passive"))
    )
    (net (code "110") (name "unconnected-(J2-ID-Pad4)") (class "Default")
      (node (ref "J2") (pin "4") (pinfunction "ID_4") (pintype "passive+no_connect"))
    )
    (net (code "111") (name "unconnected-(U8-RESERVED-Pad19)") (class "Default")
      (node (ref "U8") (pin "19") (pinfunction "RESERVED_19") (pintype "passive+no_connect"))
    )
  )
)
